# PROC010B_Pwr_RST_LEDs.net
KiCad netlist of a schematic drawn in Altium Designer
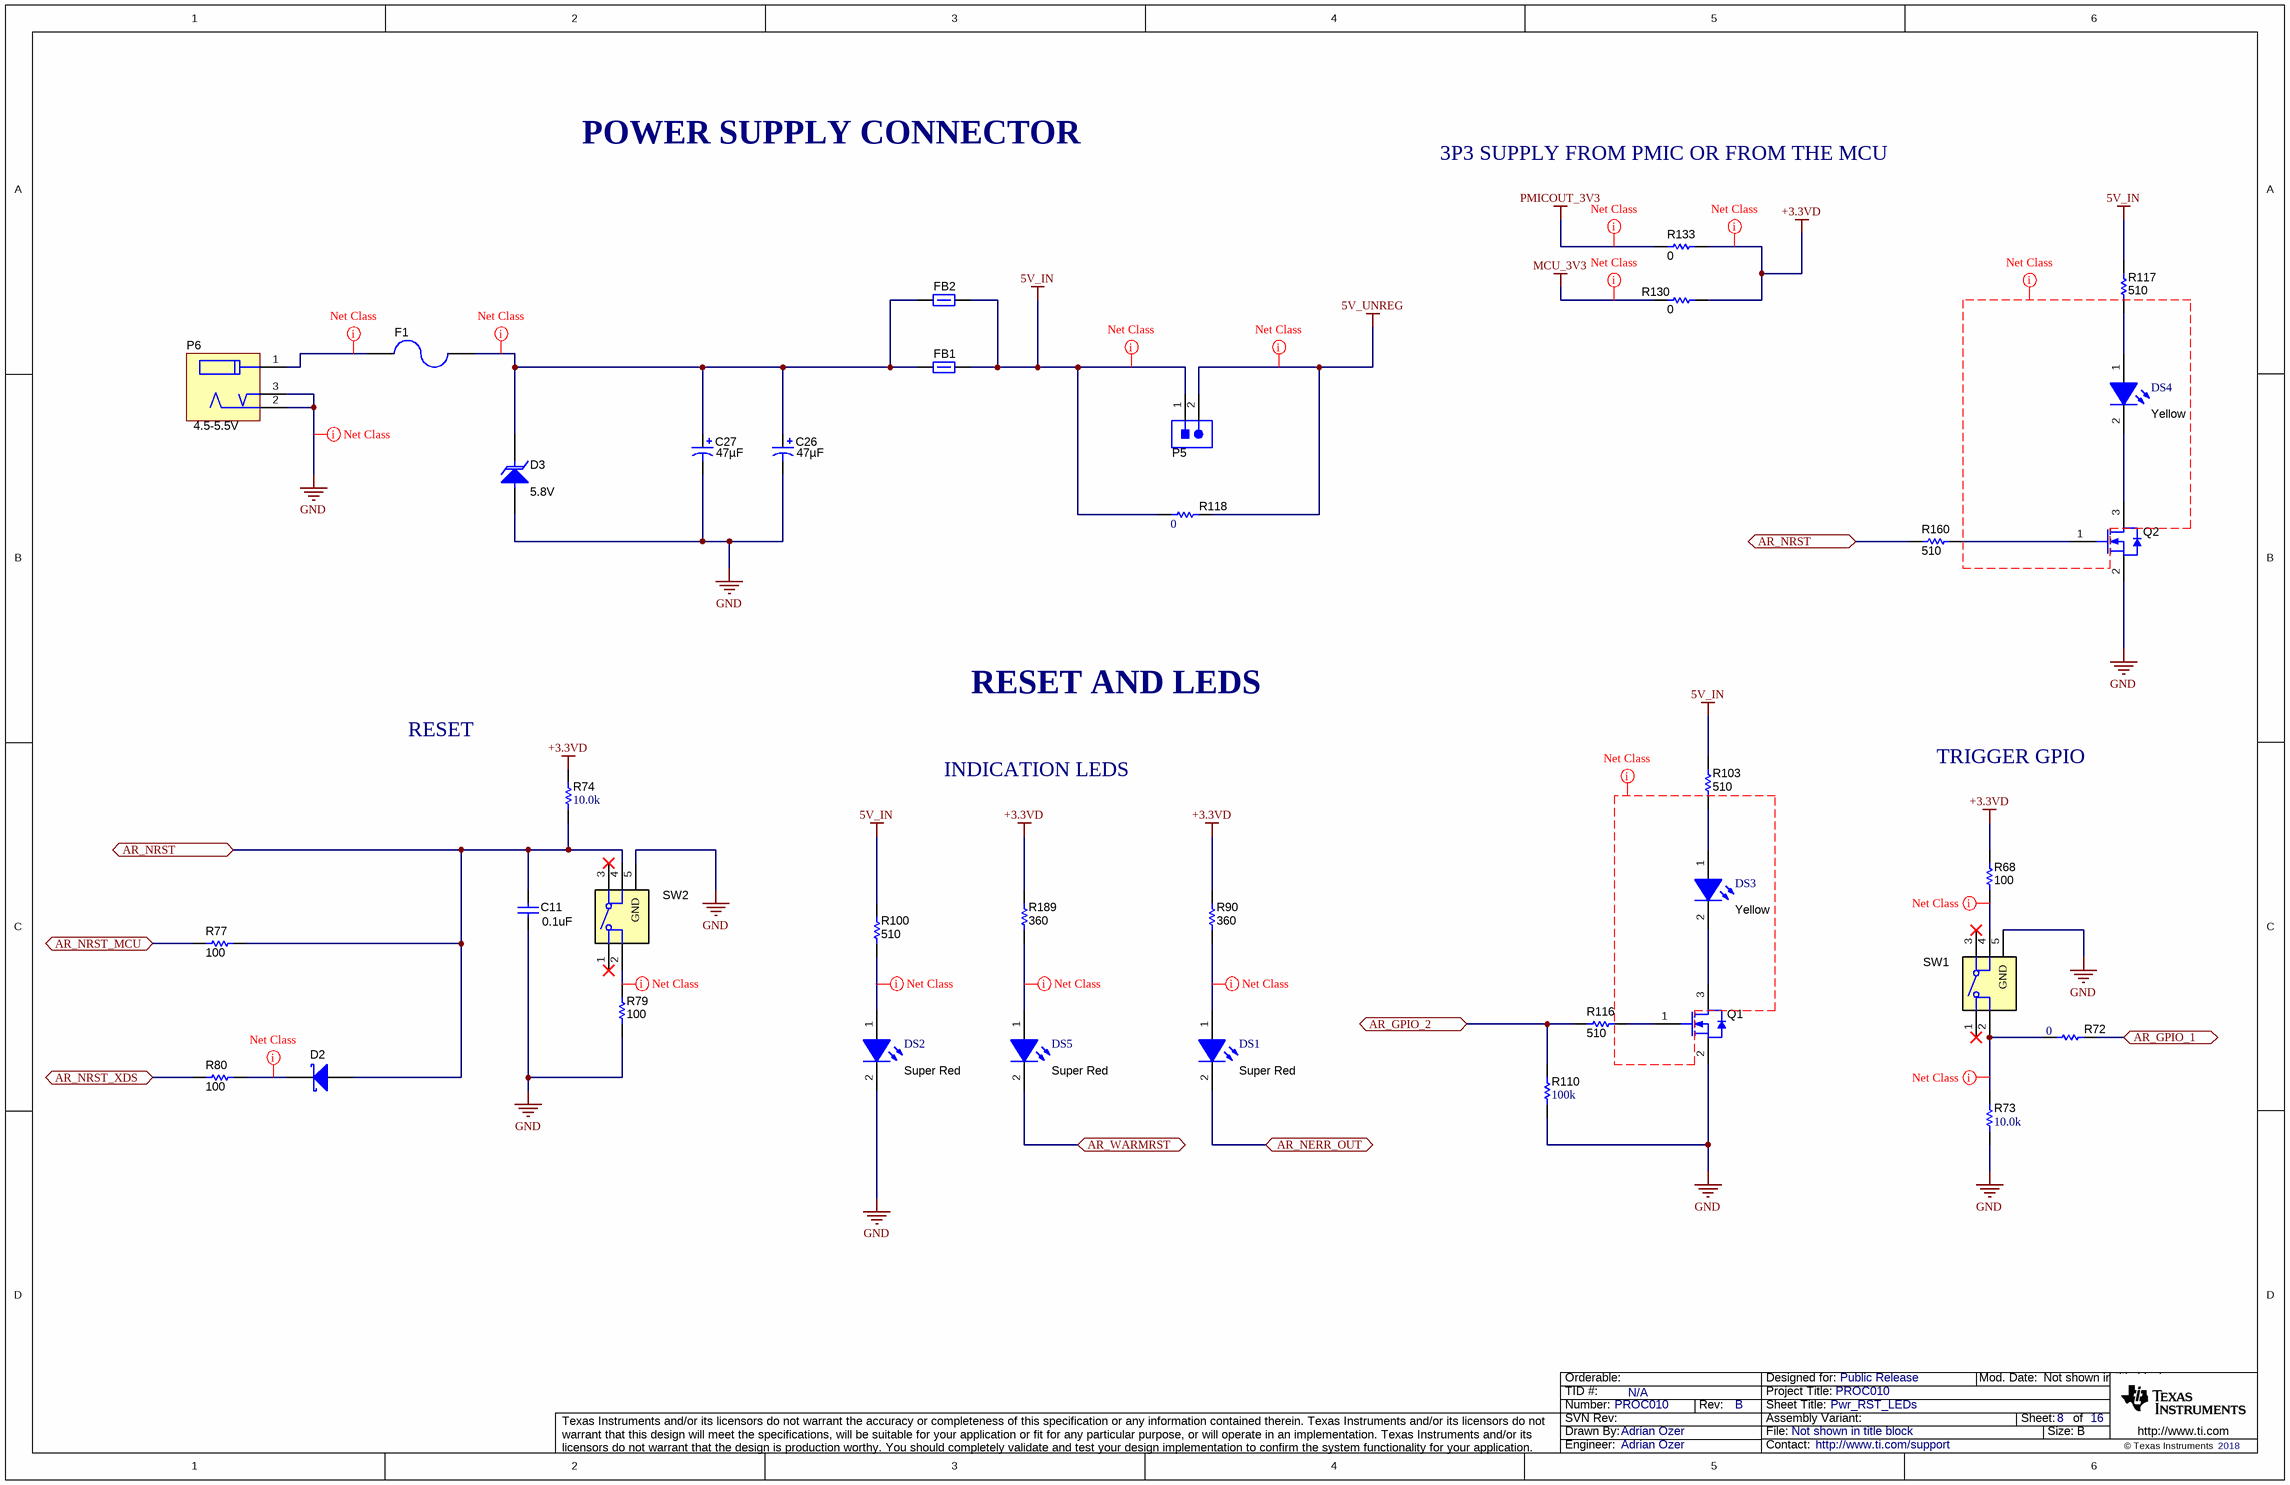
[diagram p0: PROC010B_Pwr_RST_LEDs.SchDoc]

(export (version "E")
  (design (tool "Eeschema 10.0.6"))
  (components
    (comp (ref "C11")
      (value "GCM155R71C104KA55D")
      (footprint "0402L")
      (description "CAP, CERM, 0.1 uF, 16 V, +/- 10%, X7R, 0402")
      (fields
        (field (name "MANUFACTURER") "MuRata")
        (field (name "VALUEDISPLAYED") "0.1uF")
        (field (name "PUBLISHER") "Texas Instruments")
      )
      (libsource (lib "Altium Vault - TI") (part "Capacitor"))
    )
    (comp (ref "C26")
      (value "T491B476K010AT")
      (footprint "3528-21")
      (description "CAP, TA, 47 µF, 10 V, +/- 10%, SMD")
      (fields (field (name "MANUFACTURER") "Kemet") (field (name "VALUEDISPLAYED") "47µF"))
      (libsource (lib "Altium Vault - TI") (part "Cap_Polarized"))
    )
    (comp (ref "C27")
      (value "T491B476K010AT")
      (footprint "3528-21")
      (description "CAP, TA, 47 µF, 10 V, +/- 10%, SMD")
      (fields (field (name "MANUFACTURER") "Kemet") (field (name "VALUEDISPLAYED") "47µF"))
      (libsource (lib "Altium Vault - TI") (part "Cap_Polarized"))
    )
    (comp (ref "D2")
      (value "SMS3923-040LF")
      (footprint "SOD-882")
      (description "Diode, Schottky,  V, 0.01 A, SOD-882")
      (fields (field (name "MANUFACTURER") "Skyworks Solutions"))
      (libsource (lib "Altium Vault - TI") (part "CMP-0078187-1"))
    )
    (comp (ref "D3")
      (value "5.8V")
      (footprint "SMB")
      (description "Diode, TVS, Uni, 5.8 V, 10.5 Vc, AEC-Q101, SMB")
      (fields (field (name "MANUFACTURER") "Littelfuse") (field (name "PARTNUMBER") "SZP6SMB6.8AT3G"))
      (libsource (lib "Altium Vault - TI") (part "Diode_TVS_Uni"))
    )
    (comp (ref "DS1")
      (value "Super Red")
      (footprint "SML-LX0603SRW_SuperRed")
      (description "LED, Super Red, SMD")
      (fields
        (field (name "MANUFACTURER") "Lumex")
        (field (name "PARTNUMBER") "SML-LX0603SRW-TR")
        (field (name "PUBLISHER") "Texas Instruments")
      )
      (libsource (lib "Altium Vault - TI") (part "CMP-0002876-1"))
    )
    (comp (ref "DS2")
      (value "Super Red")
      (footprint "SML-LX0603SRW_SuperRed")
      (description "LED, Super Red, SMD")
      (fields
        (field (name "MANUFACTURER") "Lumex")
        (field (name "PARTNUMBER") "SML-LX0603SRW-TR")
        (field (name "PUBLISHER") "Texas Instruments")
      )
      (libsource (lib "Altium Vault - TI") (part "CMP-0002876-1"))
    )
    (comp (ref "DS3")
      (value "Yellow")
      (footprint "SML-E1_Yellow")
      (description "LED, Yellow, SMD")
      (fields
        (field (name "MANUFACTURER") "Rohm")
        (field (name "PARTNUMBER") "SML-E12Y8WT86")
        (field (name "PUBLISHER") "Texas Instruments")
      )
      (libsource (lib "Altium Vault - TI") (part "LED"))
    )
    (comp (ref "DS4")
      (value "Yellow")
      (footprint "SML-E1_Yellow")
      (description "LED, Yellow, SMD")
      (fields
        (field (name "MANUFACTURER") "Rohm")
        (field (name "PARTNUMBER") "SML-E12Y8WT86")
        (field (name "PUBLISHER") "Texas Instruments")
      )
      (libsource (lib "Altium Vault - TI") (part "CMP-0002977-2"))
    )
    (comp (ref "DS5")
      (value "Super Red")
      (footprint "SML-LX0603SRW_SuperRed")
      (description "LED, Super Red, SMD")
      (fields
        (field (name "MANUFACTURER") "Lumex")
        (field (name "PARTNUMBER") "SML-LX0603SRW-TR")
        (field (name "PUBLISHER") "Texas Instruments")
      )
      (libsource (lib "Altium Vault - TI") (part "CMP-0002876-1"))
    )
    (comp (ref "F1")
      (value "0440005.WR")
      (footprint "1206")
      (description "Fuse, 5 A, 32VAC/VDC, SMD")
      (fields (field (name "MANUFACTURER") "Littelfuse"))
      (libsource (lib "Altium Vault - TI") (part "Fuse"))
    )
    (comp (ref "FB1")
      (value "BLM21PG300SH1D")
      (footprint "0805_HV")
      (description "Ferrite Bead, 30 ohm @ 100 MHz, 4 A, 0805")
      (fields (field (name "MANUFACTURER") "MuRata") (field (name "PUBLISHER") "Texas Instruments"))
      (libsource (lib "Altium Vault - TI") (part "CMP-0003364-1"))
    )
    (comp (ref "FB2")
      (value "BLM21PG300SH1D")
      (footprint "0805_HV")
      (description "Ferrite Bead, 30 ohm @ 100 MHz, 4 A, 0805")
      (fields (field (name "MANUFACTURER") "MuRata") (field (name "PUBLISHER") "Texas Instruments"))
      (libsource (lib "Altium Vault - TI") (part "CMP-0003364-1"))
    )
    (comp (ref "P5")
      (value "TSW-102-07-G-S")
      (footprint "TSW-102-07-G-S")
      (description "Header, 100mil, 2x1, Gold, TH")
      (fields (field (name "MANUFACTURER") "Samtec"))
      (libsource (lib "Altium Vault - TI") (part "Header_2x1"))
    )
    (comp (ref "P6")
      (value "PJ-002AH")
      (footprint "CUI_PJ-002AH")
      (description "DC POWER JACK, R/A, TH")
      (fields (field (name "VOLTAGE_V") "4.5-5.5V") (field (name "MANUFACTURER") "CUI Inc."))
      (libsource (lib "Altium Vault - TI") (part "CONN_DC JACK"))
    )
    (comp (ref "Q1")
      (value "BSS123")
      (footprint "SOT-23")
      (description "MOSFET, N-CH, 100 V, 0.17 A, SOT-23")
      (fields
        (field (name "MANUFACTURER") "Fairchild Semiconductor")
        (field (name "PUBLISHER") "Texas Instruments")
      )
      (libsource (lib "Altium Vault - TI") (part "MOSFET_N_D3G1S2"))
    )
    (comp (ref "Q2")
      (value "BSS123")
      (footprint "SOT-23")
      (description "MOSFET, N-CH, 100 V, 0.17 A, SOT-23")
      (fields
        (field (name "MANUFACTURER") "Fairchild Semiconductor")
        (field (name "PUBLISHER") "Texas Instruments")
      )
      (libsource (lib "Altium Vault - TI") (part "MOSFET_N_D3G1S2"))
    )
    (comp (ref "R68")
      (value "ERJ-2GEJ101X")
      (footprint "0402L")
      (description "RES, 100, 5%, 0.1 W, AEC-Q200 Grade 0, 0402")
      (fields
        (field (name "MANUFACTURER") "Panasonic")
        (field (name "VALUEDISPLAYED") "100")
        (field (name "PUBLISHER") "Texas Instruments")
      )
      (libsource (lib "Altium Vault - TI") (part "Resistor"))
    )
    (comp (ref "R72")
      (value "CRCW02010000Z0ED")
      (footprint "0201_Silk")
      (description "RES, 0, 5%, 0.05 W, 0201")
      (fields (field (name "MANUFACTURER") "Vishay-Dale") (field (name "VALUEDISPLAYED") "0"))
      (libsource (lib "Altium Vault - TI") (part "Resistor"))
    )
    (comp (ref "R73")
      (value "CRCW040210K0FKED")
      (footprint "0402L")
      (description "RES, 10.0 k, 1%, 0.063 W, AEC-Q200 Grade 0, 0402")
      (fields (field (name "MANUFACTURER") "Vishay-Dale") (field (name "VALUEDISPLAYED") "10.0k"))
      (libsource (lib "Altium Vault - TI") (part "Resistor"))
    )
    (comp (ref "R74")
      (value "CRCW040210K0FKED")
      (footprint "0402L")
      (description "RES, 10.0 k, 1%, 0.063 W, AEC-Q200 Grade 0, 0402")
      (fields (field (name "MANUFACTURER") "Vishay-Dale") (field (name "VALUEDISPLAYED") "10.0k"))
      (libsource (lib "Altium Vault - TI") (part "Resistor"))
    )
    (comp (ref "R77")
      (value "ERJ-2GEJ101X")
      (footprint "0402L")
      (description "RES, 100, 5%, 0.1 W, AEC-Q200 Grade 0, 0402")
      (fields
        (field (name "MANUFACTURER") "Panasonic")
        (field (name "VALUEDISPLAYED") "100")
        (field (name "PUBLISHER") "Texas Instruments")
      )
      (libsource (lib "Altium Vault - TI") (part "Resistor"))
    )
    (comp (ref "R79")
      (value "ERJ-2GEJ101X")
      (footprint "0402L")
      (description "RES, 100, 5%, 0.1 W, AEC-Q200 Grade 0, 0402")
      (fields
        (field (name "MANUFACTURER") "Panasonic")
        (field (name "VALUEDISPLAYED") "100")
        (field (name "PUBLISHER") "Texas Instruments")
      )
      (libsource (lib "Altium Vault - TI") (part "Resistor"))
    )
    (comp (ref "R80")
      (value "ERJ-2GEJ101X")
      (footprint "0402L")
      (description "RES, 100, 5%, 0.1 W, AEC-Q200 Grade 0, 0402")
      (fields
        (field (name "MANUFACTURER") "Panasonic")
        (field (name "VALUEDISPLAYED") "100")
        (field (name "PUBLISHER") "Texas Instruments")
      )
      (libsource (lib "Altium Vault - TI") (part "Resistor"))
    )
    (comp (ref "R90")
      (value "ERJ-2GEJ361X")
      (footprint "0402L")
      (description "RES, 360, 5%, 0.1 W, AEC-Q200 Grade 0, 0402")
      (fields (field (name "MANUFACTURER") "Panasonic") (field (name "VALUEDISPLAYED") "360"))
      (libsource (lib "Altium Vault - TI") (part "Resistor"))
    )
    (comp (ref "R100")
      (value "ERJ-2GEJ511X")
      (footprint "0402L")
      (description "RES, 510, 5%, 0.1 W, AEC-Q200 Grade 0, 0402")
      (fields (field (name "MANUFACTURER") "Panasonic") (field (name "VALUEDISPLAYED") "510"))
      (libsource (lib "Altium Vault - TI") (part "Resistor"))
    )
    (comp (ref "R103")
      (value "ERJ-2GEJ511X")
      (footprint "0402L")
      (description "RES, 510, 5%, 0.1 W, AEC-Q200 Grade 0, 0402")
      (fields (field (name "MANUFACTURER") "Panasonic") (field (name "VALUEDISPLAYED") "510"))
      (libsource (lib "Altium Vault - TI") (part "Resistor"))
    )
    (comp (ref "R110")
      (value "CRCW0402100KFKED")
      (footprint "0402L")
      (description "RES, 100 k, 1%, 0.063 W, AEC-Q200 Grade 0, 0402")
      (fields (field (name "MANUFACTURER") "Vishay-Dale") (field (name "VALUEDISPLAYED") "100k"))
      (libsource (lib "Altium Vault - TI") (part "Resistor"))
    )
    (comp (ref "R116")
      (value "ERJ-2GEJ511X")
      (footprint "0402L")
      (description "RES, 510, 5%, 0.1 W, AEC-Q200 Grade 0, 0402")
      (fields (field (name "MANUFACTURER") "Panasonic") (field (name "VALUEDISPLAYED") "510"))
      (libsource (lib "Altium Vault - TI") (part "Resistor"))
    )
    (comp (ref "R117")
      (value "ERJ-2GEJ511X")
      (footprint "0402L")
      (description "RES, 510, 5%, 0.1 W, AEC-Q200 Grade 0, 0402")
      (fields (field (name "MANUFACTURER") "Panasonic") (field (name "VALUEDISPLAYED") "510"))
      (libsource (lib "Altium Vault - TI") (part "Resistor"))
    )
    (comp (ref "R118")
      (value "CRCW20100000Z0EF")
      (footprint "2010")
      (description "RES, 0, 5%, 0.75 W, AEC-Q200 Grade 0, 2010")
      (fields (field (name "MANUFACTURER") "Vishay-Dale") (field (name "VALUEDISPLAYED") "0"))
      (libsource (lib "Altium Vault - TI") (part "Resistor"))
    )
    (comp (ref "R130")
      (value "MCT06030Z0000ZP500")
      (footprint "0603")
      (description "RES, 0, 5%, 0.125 W, 0603")
      (fields
        (field (name "MANUFACTURER") "Vishay/Beyschlag")
        (field (name "VALUEDISPLAYED") "0")
        (field (name "PUBLISHER") "Texas Instruments")
      )
      (libsource (lib "Altium Vault - TI") (part "CMP-0025884-3"))
    )
    (comp (ref "R133")
      (value "MCT06030Z0000ZP500")
      (footprint "0603")
      (description "RES, 0, 5%, 0.125 W, 0603")
      (fields
        (field (name "MANUFACTURER") "Vishay/Beyschlag")
        (field (name "VALUEDISPLAYED") "0")
        (field (name "PUBLISHER") "Texas Instruments")
      )
      (libsource (lib "Altium Vault - TI") (part "Resistor"))
    )
    (comp (ref "R160")
      (value "ERJ-2GEJ511X")
      (footprint "0402L")
      (description "RES, 510, 5%, 0.1 W, AEC-Q200 Grade 0, 0402")
      (fields (field (name "MANUFACTURER") "Panasonic") (field (name "VALUEDISPLAYED") "510"))
      (libsource (lib "Altium Vault - TI") (part "Resistor"))
    )
    (comp (ref "R189")
      (value "ERJ-2GEJ361X")
      (footprint "0402L")
      (description "RES, 360, 5%, 0.1 W, AEC-Q200 Grade 0, 0402")
      (fields (field (name "MANUFACTURER") "Panasonic") (field (name "VALUEDISPLAYED") "360"))
      (libsource (lib "Altium Vault - TI") (part "Resistor"))
    )
    (comp (ref "SW1")
      (value "KMR243GLFG")
      (footprint "SW_KMR243GLFG")
      (description "Switch, SPST-NO, Off-Mom, 0.01 A, 32 VDC, SMD")
      (fields (field (name "MANUFACTURER") "C&K Components") (field (name "PUBLISHER") "Texas Instruments"))
      (libsource (lib "Altium Vault - TI") (part "CMP-0002325-1"))
    )
    (comp (ref "SW2")
      (value "KMR243GLFG")
      (footprint "SW_KMR243GLFG")
      (description "Switch, SPST-NO, Off-Mom, 0.01 A, 32 VDC, SMD")
      (fields (field (name "MANUFACTURER") "C&K Components") (field (name "PUBLISHER") "Texas Instruments"))
      (libsource (lib "Altium Vault - TI") (part "CMP-0002325-1"))
    )
  )
  (nets
    (net (code "1") (name "+3.3VD") (class "Default")
      (node (ref "R130") (pin "2") (pinfunction "2_2") (pintype "passive"))
      (node (ref "R133") (pin "2") (pinfunction "2_2") (pintype "passive"))
      (node (ref "R189") (pin "2") (pinfunction "2_2") (pintype "passive"))
      (node (ref "R68") (pin "2") (pinfunction "2_2") (pintype "passive"))
      (node (ref "R74") (pin "2") (pinfunction "2_2") (pintype "passive"))
      (node (ref "R90") (pin "2") (pinfunction "2_2") (pintype "passive"))
    )
    (net (code "2") (name "/AR_GPIO_1") (class "Default")
      (node (ref "R72") (pin "2") (pinfunction "2_2") (pintype "passive"))
    )
    (net (code "3") (name "/AR_GPIO_2") (class "Default")
      (node (ref "R110") (pin "2") (pinfunction "2_2") (pintype "passive"))
      (node (ref "R116") (pin "1") (pinfunction "1_1") (pintype "passive"))
    )
    (net (code "4") (name "/AR_NERR_OUT") (class "Default")
      (node (ref "DS1") (pin "2") (pinfunction "K_2") (pintype "passive"))
    )
    (net (code "5") (name "/AR_NRST") (class "Default")
      (node (ref "C11") (pin "2") (pinfunction "2_2") (pintype "passive"))
      (node (ref "D2") (pin "2") (pinfunction "A_2") (pintype "passive"))
      (node (ref "R160") (pin "1") (pinfunction "1_1") (pintype "passive"))
      (node (ref "R74") (pin "1") (pinfunction "1_1") (pintype "passive"))
      (node (ref "R77") (pin "2") (pinfunction "2_2") (pintype "passive"))
      (node (ref "SW2") (pin "4") (pinfunction "4_4") (pintype "passive"))
    )
    (net (code "6") (name "/AR_NRST_MCU") (class "Default")
      (node (ref "R77") (pin "1") (pinfunction "1_1") (pintype "passive"))
    )
    (net (code "7") (name "/AR_NRST_XDS") (class "Default")
      (node (ref "R80") (pin "1") (pinfunction "1_1") (pintype "passive"))
    )
    (net (code "8") (name "/AR_WARMRST") (class "Default")
      (node (ref "DS5") (pin "2") (pinfunction "K_2") (pintype "passive"))
    )
    (net (code "9") (name "5V_IN") (class "Default")
      (node (ref "FB1") (pin "2") (pinfunction "2_2") (pintype "passive"))
      (node (ref "FB2") (pin "2") (pinfunction "2_2") (pintype "passive"))
      (node (ref "P5") (pin "1") (pinfunction "1_1") (pintype "passive"))
      (node (ref "R100") (pin "2") (pinfunction "2_2") (pintype "passive"))
      (node (ref "R103") (pin "2") (pinfunction "2_2") (pintype "passive"))
      (node (ref "R117") (pin "2") (pinfunction "2_2") (pintype "passive"))
      (node (ref "R118") (pin "1") (pinfunction "1_1") (pintype "passive"))
    )
    (net (code "10") (name "5V_UNREG") (class "Default")
      (node (ref "P5") (pin "2") (pinfunction "2_2") (pintype "passive"))
      (node (ref "R118") (pin "2") (pinfunction "2_2") (pintype "passive"))
    )
    (net (code "11") (name "GND") (class "Default")
      (node (ref "C11") (pin "1") (pinfunction "1_1") (pintype "passive"))
      (node (ref "C26") (pin "2") (pinfunction "-_2") (pintype "passive"))
      (node (ref "C27") (pin "2") (pinfunction "-_2") (pintype "passive"))
      (node (ref "D3") (pin "2") (pinfunction "A_2") (pintype "passive"))
      (node (ref "DS2") (pin "2") (pinfunction "K_2") (pintype "passive"))
      (node (ref "P6") (pin "2") (pinfunction "2_2") (pintype "passive"))
      (node (ref "P6") (pin "3") (pinfunction "3_3") (pintype "passive"))
      (node (ref "Q1") (pin "2") (pinfunction "S_2") (pintype "passive"))
      (node (ref "Q2") (pin "2") (pinfunction "S_2") (pintype "passive"))
      (node (ref "R110") (pin "1") (pinfunction "1_1") (pintype "passive"))
      (node (ref "R73") (pin "1") (pinfunction "1_1") (pintype "passive"))
      (node (ref "R79") (pin "1") (pinfunction "1_1") (pintype "passive"))
      (node (ref "SW1") (pin "5") (pinfunction "GND_5") (pintype "passive"))
      (node (ref "SW2") (pin "5") (pinfunction "GND_5") (pintype "passive"))
    )
    (net (code "12") (name "MCU_3V3") (class "Default")
      (node (ref "R130") (pin "1") (pinfunction "1_1") (pintype "passive"))
    )
    (net (code "13") (name "Net-(C26-+)") (class "Default")
      (node (ref "C26") (pin "1") (pinfunction "+_1") (pintype "passive"))
      (node (ref "C27") (pin "1") (pinfunction "+_1") (pintype "passive"))
      (node (ref "D3") (pin "1") (pinfunction "K_1") (pintype "passive"))
      (node (ref "F1") (pin "1") (pinfunction "1_1") (pintype "passive"))
      (node (ref "FB1") (pin "1") (pinfunction "1_1") (pintype "passive"))
      (node (ref "FB2") (pin "1") (pinfunction "1_1") (pintype "passive"))
    )
    (net (code "14") (name "Net-(D2-K)") (class "Default")
      (node (ref "D2") (pin "1") (pinfunction "K_1") (pintype "passive"))
      (node (ref "R80") (pin "2") (pinfunction "2_2") (pintype "passive"))
    )
    (net (code "15") (name "Net-(DS1-A)") (class "Default")
      (node (ref "DS1") (pin "1") (pinfunction "A_1") (pintype "passive"))
      (node (ref "R90") (pin "1") (pinfunction "1_1") (pintype "passive"))
    )
    (net (code "16") (name "Net-(DS2-A)") (class "Default")
      (node (ref "DS2") (pin "1") (pinfunction "A_1") (pintype "passive"))
      (node (ref "R100") (pin "1") (pinfunction "1_1") (pintype "passive"))
    )
    (net (code "17") (name "Net-(DS3-A)") (class "Default")
      (node (ref "DS3") (pin "1") (pinfunction "A_1") (pintype "passive"))
      (node (ref "R103") (pin "1") (pinfunction "1_1") (pintype "passive"))
    )
    (net (code "18") (name "Net-(DS3-K)") (class "Default")
      (node (ref "DS3") (pin "2") (pinfunction "K_2") (pintype "passive"))
      (node (ref "Q1") (pin "3") (pinfunction "D_3") (pintype "passive"))
    )
    (net (code "19") (name "Net-(DS4-A)") (class "Default")
      (node (ref "DS4") (pin "1") (pinfunction "A_1") (pintype "passive"))
      (node (ref "R117") (pin "1") (pinfunction "1_1") (pintype "passive"))
    )
    (net (code "20") (name "Net-(DS4-K)") (class "Default")
      (node (ref "DS4") (pin "2") (pinfunction "K_2") (pintype "passive"))
      (node (ref "Q2") (pin "3") (pinfunction "D_3") (pintype "passive"))
    )
    (net (code "21") (name "Net-(DS5-A)") (class "Default")
      (node (ref "DS5") (pin "1") (pinfunction "A_1") (pintype "passive"))
      (node (ref "R189") (pin "1") (pinfunction "1_1") (pintype "passive"))
    )
    (net (code "22") (name "Net-(F1-Pad2)") (class "Default")
      (node (ref "F1") (pin "2") (pinfunction "2_2") (pintype "passive"))
      (node (ref "P6") (pin "1") (pinfunction "1_1") (pintype "passive"))
    )
    (net (code "23") (name "Net-(Q1-G)") (class "Default")
      (node (ref "Q1") (pin "1") (pinfunction "G_1") (pintype "passive"))
      (node (ref "R116") (pin "2") (pinfunction "2_2") (pintype "passive"))
    )
    (net (code "24") (name "Net-(Q2-G)") (class "Default")
      (node (ref "Q2") (pin "1") (pinfunction "G_1") (pintype "passive"))
      (node (ref "R160") (pin "2") (pinfunction "2_2") (pintype "passive"))
    )
    (net (code "25") (name "Net-(R68-Pad1)") (class "Default")
      (node (ref "R68") (pin "1") (pinfunction "1_1") (pintype "passive"))
      (node (ref "SW1") (pin "4") (pinfunction "4_4") (pintype "passive"))
    )
    (net (code "26") (name "Net-(R72-Pad1)") (class "Default")
      (node (ref "R72") (pin "1") (pinfunction "1_1") (pintype "passive"))
      (node (ref "R73") (pin "2") (pinfunction "2_2") (pintype "passive"))
      (node (ref "SW1") (pin "2") (pinfunction "2_2") (pintype "passive"))
    )
    (net (code "27") (name "Net-(R79-Pad2)") (class "Default")
      (node (ref "R79") (pin "2") (pinfunction "2_2") (pintype "passive"))
      (node (ref "SW2") (pin "2") (pinfunction "2_2") (pintype "passive"))
    )
    (net (code "28") (name "PMICOUT_3V3") (class "Default")
      (node (ref "R133") (pin "1") (pinfunction "1_1") (pintype "passive"))
    )
    (net (code "29") (name "unconnected-(SW1-Pad1)") (class "Default")
      (node (ref "SW1") (pin "1") (pinfunction "1_1") (pintype "passive+no_connect"))
    )
    (net (code "30") (name "unconnected-(SW1-Pad3)") (class "Default")
      (node (ref "SW1") (pin "3") (pinfunction "3_3") (pintype "passive+no_connect"))
    )
    (net (code "31") (name "unconnected-(SW2-Pad1)") (class "Default")
      (node (ref "SW2") (pin "1") (pinfunction "1_1") (pintype "passive+no_connect"))
    )
    (net (code "32") (name "unconnected-(SW2-Pad3)") (class "Default")
      (node (ref "SW2") (pin "3") (pinfunction "3_3") (pintype "passive+no_connect"))
    )
  )
)
